# Signal.net
KiCad netlist of a schematic drawn in EAGLE
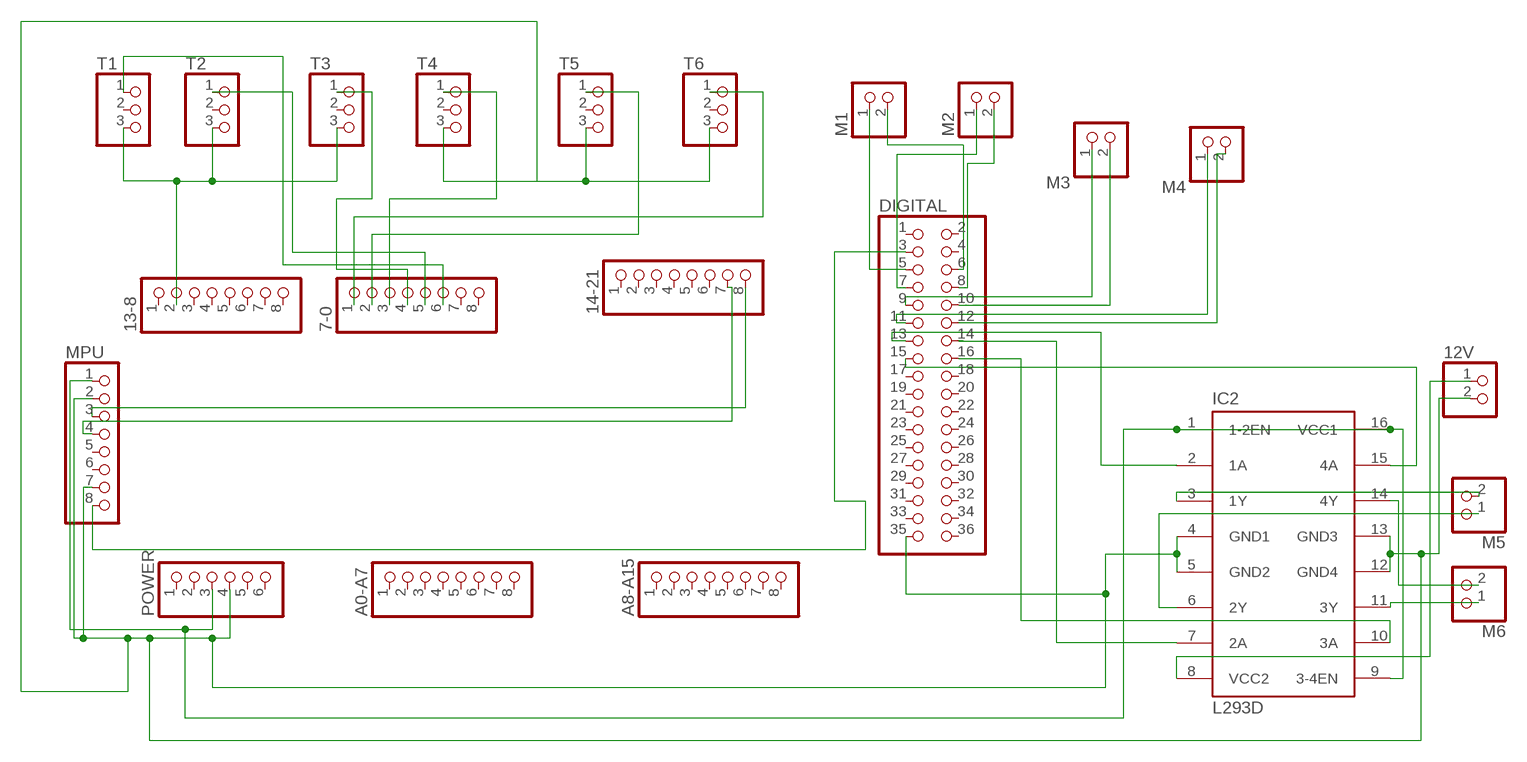
[diagram p0: schematic, sheet 1]

(export (version "E")
  (design (tool "Eeschema 10.0.6"))
  (components
    (comp (ref "7-0")
      (value "PINHD-1X8")
      (footprint "eagle-import:1X08")
      (libsource (lib "eagle-import") (part "PINHD-1X8"))
    )
    (comp (ref "12V")
      (value "PINHD-1X2")
      (footprint "eagle-import:1X02")
      (libsource (lib "eagle-import") (part "PINHD-1X2"))
    )
    (comp (ref "13-8")
      (value "PINHD-1X8")
      (footprint "eagle-import:1X08")
      (libsource (lib "eagle-import") (part "PINHD-1X8"))
    )
    (comp (ref "14-21")
      (value "PINHD-1X8")
      (footprint "eagle-import:1X08")
      (libsource (lib "eagle-import") (part "PINHD-1X8"))
    )
    (comp (ref "A0-A7")
      (value "PINHD-1X8")
      (footprint "eagle-import:1X08")
      (libsource (lib "eagle-import") (part "PINHD-1X8"))
    )
    (comp (ref "A8-A15")
      (value "PINHD-1X8")
      (footprint "eagle-import:1X08")
      (libsource (lib "eagle-import") (part "PINHD-1X8"))
    )
    (comp (ref "DIGITAL")
      (value "PINHD-2X18")
      (footprint "eagle-import:2X18")
      (libsource (lib "eagle-import") (part "PINHD-2X18"))
    )
    (comp (ref "IC2")
      (value "L293D")
      (footprint "eagle-import:DIL16")
      (libsource (lib "eagle-import") (part "L293D"))
    )
    (comp (ref "M1")
      (value "PINHD-1X2")
      (footprint "eagle-import:1X02")
      (libsource (lib "eagle-import") (part "PINHD-1X2"))
    )
    (comp (ref "M2")
      (value "PINHD-1X2")
      (footprint "eagle-import:1X02")
      (libsource (lib "eagle-import") (part "PINHD-1X2"))
    )
    (comp (ref "M3")
      (value "PINHD-1X2")
      (footprint "eagle-import:1X02")
      (libsource (lib "eagle-import") (part "PINHD-1X2"))
    )
    (comp (ref "M4")
      (value "PINHD-1X2")
      (footprint "eagle-import:1X02")
      (libsource (lib "eagle-import") (part "PINHD-1X2"))
    )
    (comp (ref "M5")
      (value "PINHD-1X2")
      (footprint "eagle-import:1X02")
      (libsource (lib "eagle-import") (part "PINHD-1X2"))
    )
    (comp (ref "M6")
      (value "PINHD-1X2")
      (footprint "eagle-import:1X02")
      (libsource (lib "eagle-import") (part "PINHD-1X2"))
    )
    (comp (ref "MPU")
      (value "PINHD-1X8")
      (footprint "eagle-import:1X08")
      (libsource (lib "eagle-import") (part "PINHD-1X8"))
    )
    (comp (ref "POWER")
      (value "PINHD-1X6")
      (footprint "eagle-import:1X06")
      (libsource (lib "eagle-import") (part "PINHD-1X6"))
    )
    (comp (ref "T1")
      (value "PINHD-1X3")
      (footprint "eagle-import:1X03")
      (libsource (lib "eagle-import") (part "PINHD-1X3"))
    )
    (comp (ref "T2")
      (value "PINHD-1X3")
      (footprint "eagle-import:1X03")
      (libsource (lib "eagle-import") (part "PINHD-1X3"))
    )
    (comp (ref "T3")
      (value "PINHD-1X3")
      (footprint "eagle-import:1X03")
      (libsource (lib "eagle-import") (part "PINHD-1X3"))
    )
    (comp (ref "T4")
      (value "PINHD-1X3")
      (footprint "eagle-import:1X03")
      (libsource (lib "eagle-import") (part "PINHD-1X3"))
    )
    (comp (ref "T5")
      (value "PINHD-1X3")
      (footprint "eagle-import:1X03")
      (libsource (lib "eagle-import") (part "PINHD-1X3"))
    )
    (comp (ref "T6")
      (value "PINHD-1X3")
      (footprint "eagle-import:1X03")
      (libsource (lib "eagle-import") (part "PINHD-1X3"))
    )
  )
  (nets
    (net (code "1") (name "Net-(7-0-Pad1)") (class "Default")
      (node (ref "7-0") (pin "1") (pinfunction "1_1") (pintype "passive"))
      (node (ref "T6") (pin "1") (pinfunction "1_1") (pintype "passive"))
    )
    (net (code "2") (name "Net-(7-0-Pad2)") (class "Default")
      (node (ref "7-0") (pin "2") (pinfunction "2_2") (pintype "passive"))
      (node (ref "T5") (pin "1") (pinfunction "1_1") (pintype "passive"))
    )
    (net (code "3") (name "Net-(7-0-Pad3)") (class "Default")
      (node (ref "7-0") (pin "3") (pinfunction "3_3") (pintype "passive"))
      (node (ref "T4") (pin "1") (pinfunction "1_1") (pintype "passive"))
    )
    (net (code "4") (name "Net-(7-0-Pad4)") (class "Default")
      (node (ref "7-0") (pin "4") (pinfunction "4_4") (pintype "passive"))
      (node (ref "T3") (pin "1") (pinfunction "1_1") (pintype "passive"))
    )
    (net (code "5") (name "Net-(7-0-Pad5)") (class "Default")
      (node (ref "7-0") (pin "5") (pinfunction "5_5") (pintype "passive"))
      (node (ref "T2") (pin "1") (pinfunction "1_1") (pintype "passive"))
    )
    (net (code "6") (name "Net-(7-0-Pad6)") (class "Default")
      (node (ref "7-0") (pin "6") (pinfunction "6_6") (pintype "passive"))
      (node (ref "T1") (pin "1") (pinfunction "1_1") (pintype "passive"))
    )
    (net (code "7") (name "Net-(13-8-Pad2)") (class "Default")
      (node (ref "13-8") (pin "2") (pinfunction "2_2") (pintype "passive"))
      (node (ref "T1") (pin "3") (pinfunction "3_3") (pintype "passive"))
      (node (ref "T2") (pin "3") (pinfunction "3_3") (pintype "passive"))
      (node (ref "T3") (pin "3") (pinfunction "3_3") (pintype "passive"))
    )
    (net (code "8") (name "Net-(14-21-Pad7)") (class "Default")
      (node (ref "14-21") (pin "7") (pinfunction "7_7") (pintype "passive"))
      (node (ref "MPU") (pin "4") (pinfunction "4_4") (pintype "passive"))
    )
    (net (code "9") (name "Net-(14-21-Pad8)") (class "Default")
      (node (ref "14-21") (pin "8") (pinfunction "8_8") (pintype "passive"))
      (node (ref "MPU") (pin "3") (pinfunction "3_3") (pintype "passive"))
    )
    (net (code "10") (name "Net-(DIGITAL-Pad3)") (class "Default")
      (node (ref "DIGITAL") (pin "3") (pinfunction "3_3") (pintype "passive"))
      (node (ref "MPU") (pin "8") (pinfunction "8_8") (pintype "passive"))
    )
    (net (code "11") (name "Net-(DIGITAL-Pad5)") (class "Default")
      (node (ref "DIGITAL") (pin "5") (pinfunction "5_5") (pintype "passive"))
      (node (ref "M1") (pin "1") (pinfunction "1_1") (pintype "passive"))
    )
    (net (code "12") (name "Net-(DIGITAL-Pad6)") (class "Default")
      (node (ref "DIGITAL") (pin "6") (pinfunction "6_6") (pintype "passive"))
      (node (ref "M1") (pin "2") (pinfunction "2_2") (pintype "passive"))
    )
    (net (code "13") (name "Net-(DIGITAL-Pad7)") (class "Default")
      (node (ref "DIGITAL") (pin "7") (pinfunction "7_7") (pintype "passive"))
      (node (ref "M2") (pin "1") (pinfunction "1_1") (pintype "passive"))
    )
    (net (code "14") (name "Net-(DIGITAL-Pad8)") (class "Default")
      (node (ref "DIGITAL") (pin "8") (pinfunction "8_8") (pintype "passive"))
      (node (ref "M2") (pin "2") (pinfunction "2_2") (pintype "passive"))
    )
    (net (code "15") (name "Net-(DIGITAL-Pad9)") (class "Default")
      (node (ref "DIGITAL") (pin "9") (pinfunction "9_9") (pintype "passive"))
      (node (ref "M3") (pin "1") (pinfunction "1_1") (pintype "passive"))
    )
    (net (code "16") (name "Net-(DIGITAL-Pad10)") (class "Default")
      (node (ref "DIGITAL") (pin "10") (pinfunction "10_10") (pintype "passive"))
      (node (ref "M3") (pin "2") (pinfunction "2_2") (pintype "passive"))
    )
    (net (code "17") (name "Net-(DIGITAL-Pad11)") (class "Default")
      (node (ref "DIGITAL") (pin "11") (pinfunction "11_11") (pintype "passive"))
      (node (ref "M4") (pin "1") (pinfunction "1_1") (pintype "passive"))
    )
    (net (code "18") (name "Net-(DIGITAL-Pad12)") (class "Default")
      (node (ref "DIGITAL") (pin "12") (pinfunction "12_12") (pintype "passive"))
      (node (ref "M4") (pin "2") (pinfunction "2_2") (pintype "passive"))
    )
    (net (code "19") (name "Net-(IC2-1-2EN)") (class "Default")
      (node (ref "IC2") (pin "1") (pinfunction "1-2EN_1") (pintype "input"))
      (node (ref "IC2") (pin "16") (pinfunction "VCC1_16") (pintype "power_in"))
      (node (ref "IC2") (pin "9") (pinfunction "3-4EN_9") (pintype "input"))
      (node (ref "MPU") (pin "1") (pinfunction "1_1") (pintype "passive"))
      (node (ref "POWER") (pin "3") (pinfunction "3_3") (pintype "passive"))
    )
    (net (code "20") (name "Net-(IC2-1A)") (class "Default")
      (node (ref "DIGITAL") (pin "13") (pinfunction "13_13") (pintype "passive"))
      (node (ref "IC2") (pin "2") (pinfunction "1A_2") (pintype "input"))
    )
    (net (code "21") (name "Net-(IC2-1Y)") (class "Default")
      (node (ref "IC2") (pin "3") (pinfunction "1Y_3") (pintype "output"))
      (node (ref "M5") (pin "2") (pinfunction "2_2") (pintype "passive"))
    )
    (net (code "22") (name "Net-(IC2-2A)") (class "Default")
      (node (ref "DIGITAL") (pin "14") (pinfunction "14_14") (pintype "passive"))
      (node (ref "IC2") (pin "7") (pinfunction "2A_7") (pintype "input"))
    )
    (net (code "23") (name "Net-(IC2-2Y)") (class "Default")
      (node (ref "IC2") (pin "6") (pinfunction "2Y_6") (pintype "output"))
      (node (ref "M5") (pin "1") (pinfunction "1_1") (pintype "passive"))
    )
    (net (code "24") (name "Net-(IC2-3A)") (class "Default")
      (node (ref "DIGITAL") (pin "16") (pinfunction "16_16") (pintype "passive"))
      (node (ref "IC2") (pin "10") (pinfunction "3A_10") (pintype "input"))
    )
    (net (code "25") (name "Net-(IC2-3Y)") (class "Default")
      (node (ref "IC2") (pin "11") (pinfunction "3Y_11") (pintype "output"))
      (node (ref "M6") (pin "1") (pinfunction "1_1") (pintype "passive"))
    )
    (net (code "26") (name "Net-(IC2-4A)") (class "Default")
      (node (ref "DIGITAL") (pin "15") (pinfunction "15_15") (pintype "passive"))
      (node (ref "IC2") (pin "15") (pinfunction "4A_15") (pintype "input"))
    )
    (net (code "27") (name "Net-(IC2-4Y)") (class "Default")
      (node (ref "IC2") (pin "14") (pinfunction "4Y_14") (pintype "output"))
      (node (ref "M6") (pin "2") (pinfunction "2_2") (pintype "passive"))
    )
    (net (code "28") (name "Net-(IC2-GND1)") (class "Default")
      (node (ref "12V") (pin "2") (pinfunction "2_2") (pintype "passive"))
      (node (ref "DIGITAL") (pin "35") (pinfunction "35_35") (pintype "passive"))
      (node (ref "IC2") (pin "12") (pinfunction "GND4_12") (pintype "power_in"))
      (node (ref "IC2") (pin "13") (pinfunction "GND3_13") (pintype "power_in"))
      (node (ref "IC2") (pin "4") (pinfunction "GND1_4") (pintype "power_in"))
      (node (ref "IC2") (pin "5") (pinfunction "GND2_5") (pintype "power_in"))
      (node (ref "MPU") (pin "2") (pinfunction "2_2") (pintype "passive"))
      (node (ref "MPU") (pin "7") (pinfunction "7_7") (pintype "passive"))
      (node (ref "POWER") (pin "4") (pinfunction "4_4") (pintype "passive"))
      (node (ref "T4") (pin "3") (pinfunction "3_3") (pintype "passive"))
      (node (ref "T5") (pin "3") (pinfunction "3_3") (pintype "passive"))
      (node (ref "T6") (pin "3") (pinfunction "3_3") (pintype "passive"))
    )
    (net (code "29") (name "Net-(IC2-VCC2)") (class "Default")
      (node (ref "12V") (pin "1") (pinfunction "1_1") (pintype "passive"))
      (node (ref "IC2") (pin "8") (pinfunction "VCC2_8") (pintype "power_in"))
    )
    (net (code "30") (name "unconnected-(7-0-Pad7)") (class "Default")
      (node (ref "7-0") (pin "7") (pinfunction "7_7") (pintype "passive"))
    )
    (net (code "31") (name "unconnected-(7-0-Pad8)") (class "Default")
      (node (ref "7-0") (pin "8") (pinfunction "8_8") (pintype "passive"))
    )
    (net (code "32") (name "unconnected-(13-8-Pad1)") (class "Default")
      (node (ref "13-8") (pin "1") (pinfunction "1_1") (pintype "passive"))
    )
    (net (code "33") (name "unconnected-(13-8-Pad3)") (class "Default")
      (node (ref "13-8") (pin "3") (pinfunction "3_3") (pintype "passive"))
    )
    (net (code "34") (name "unconnected-(13-8-Pad4)") (class "Default")
      (node (ref "13-8") (pin "4") (pinfunction "4_4") (pintype "passive"))
    )
    (net (code "35") (name "unconnected-(13-8-Pad5)") (class "Default")
      (node (ref "13-8") (pin "5") (pinfunction "5_5") (pintype "passive"))
    )
    (net (code "36") (name "unconnected-(13-8-Pad6)") (class "Default")
      (node (ref "13-8") (pin "6") (pinfunction "6_6") (pintype "passive"))
    )
    (net (code "37") (name "unconnected-(13-8-Pad7)") (class "Default")
      (node (ref "13-8") (pin "7") (pinfunction "7_7") (pintype "passive"))
    )
    (net (code "38") (name "unconnected-(13-8-Pad8)") (class "Default")
      (node (ref "13-8") (pin "8") (pinfunction "8_8") (pintype "passive"))
    )
    (net (code "39") (name "unconnected-(14-21-Pad1)") (class "Default")
      (node (ref "14-21") (pin "1") (pinfunction "1_1") (pintype "passive"))
    )
    (net (code "40") (name "unconnected-(14-21-Pad2)") (class "Default")
      (node (ref "14-21") (pin "2") (pinfunction "2_2") (pintype "passive"))
    )
    (net (code "41") (name "unconnected-(14-21-Pad3)") (class "Default")
      (node (ref "14-21") (pin "3") (pinfunction "3_3") (pintype "passive"))
    )
    (net (code "42") (name "unconnected-(14-21-Pad4)") (class "Default")
      (node (ref "14-21") (pin "4") (pinfunction "4_4") (pintype "passive"))
    )
    (net (code "43") (name "unconnected-(14-21-Pad5)") (class "Default")
      (node (ref "14-21") (pin "5") (pinfunction "5_5") (pintype "passive"))
    )
    (net (code "44") (name "unconnected-(14-21-Pad6)") (class "Default")
      (node (ref "14-21") (pin "6") (pinfunction "6_6") (pintype "passive"))
    )
    (net (code "45") (name "unconnected-(A0-A7-Pad1)") (class "Default")
      (node (ref "A0-A7") (pin "1") (pinfunction "1_1") (pintype "passive"))
    )
    (net (code "46") (name "unconnected-(A0-A7-Pad2)") (class "Default")
      (node (ref "A0-A7") (pin "2") (pinfunction "2_2") (pintype "passive"))
    )
    (net (code "47") (name "unconnected-(A0-A7-Pad3)") (class "Default")
      (node (ref "A0-A7") (pin "3") (pinfunction "3_3") (pintype "passive"))
    )
    (net (code "48") (name "unconnected-(A0-A7-Pad4)") (class "Default")
      (node (ref "A0-A7") (pin "4") (pinfunction "4_4") (pintype "passive"))
    )
    (net (code "49") (name "unconnected-(A0-A7-Pad5)") (class "Default")
      (node (ref "A0-A7") (pin "5") (pinfunction "5_5") (pintype "passive"))
    )
    (net (code "50") (name "unconnected-(A0-A7-Pad6)") (class "Default")
      (node (ref "A0-A7") (pin "6") (pinfunction "6_6") (pintype "passive"))
    )
    (net (code "51") (name "unconnected-(A0-A7-Pad7)") (class "Default")
      (node (ref "A0-A7") (pin "7") (pinfunction "7_7") (pintype "passive"))
    )
    (net (code "52") (name "unconnected-(A0-A7-Pad8)") (class "Default")
      (node (ref "A0-A7") (pin "8") (pinfunction "8_8") (pintype "passive"))
    )
    (net (code "53") (name "unconnected-(A8-A15-Pad1)") (class "Default")
      (node (ref "A8-A15") (pin "1") (pinfunction "1_1") (pintype "passive"))
    )
    (net (code "54") (name "unconnected-(A8-A15-Pad2)") (class "Default")
      (node (ref "A8-A15") (pin "2") (pinfunction "2_2") (pintype "passive"))
    )
    (net (code "55") (name "unconnected-(A8-A15-Pad3)") (class "Default")
      (node (ref "A8-A15") (pin "3") (pinfunction "3_3") (pintype "passive"))
    )
    (net (code "56") (name "unconnected-(A8-A15-Pad4)") (class "Default")
      (node (ref "A8-A15") (pin "4") (pinfunction "4_4") (pintype "passive"))
    )
    (net (code "57") (name "unconnected-(A8-A15-Pad5)") (class "Default")
      (node (ref "A8-A15") (pin "5") (pinfunction "5_5") (pintype "passive"))
    )
    (net (code "58") (name "unconnected-(A8-A15-Pad6)") (class "Default")
      (node (ref "A8-A15") (pin "6") (pinfunction "6_6") (pintype "passive"))
    )
    (net (code "59") (name "unconnected-(A8-A15-Pad7)") (class "Default")
      (node (ref "A8-A15") (pin "7") (pinfunction "7_7") (pintype "passive"))
    )
    (net (code "60") (name "unconnected-(A8-A15-Pad8)") (class "Default")
      (node (ref "A8-A15") (pin "8") (pinfunction "8_8") (pintype "passive"))
    )
    (net (code "61") (name "unconnected-(DIGITAL-Pad1)") (class "Default")
      (node (ref "DIGITAL") (pin "1") (pinfunction "1_1") (pintype "passive"))
    )
    (net (code "62") (name "unconnected-(DIGITAL-Pad2)") (class "Default")
      (node (ref "DIGITAL") (pin "2") (pinfunction "2_2") (pintype "passive"))
    )
    (net (code "63") (name "unconnected-(DIGITAL-Pad4)") (class "Default")
      (node (ref "DIGITAL") (pin "4") (pinfunction "4_4") (pintype "passive"))
    )
    (net (code "64") (name "unconnected-(DIGITAL-Pad17)") (class "Default")
      (node (ref "DIGITAL") (pin "17") (pinfunction "17_17") (pintype "passive"))
    )
    (net (code "65") (name "unconnected-(DIGITAL-Pad18)") (class "Default")
      (node (ref "DIGITAL") (pin "18") (pinfunction "18_18") (pintype "passive"))
    )
    (net (code "66") (name "unconnected-(DIGITAL-Pad19)") (class "Default")
      (node (ref "DIGITAL") (pin "19") (pinfunction "19_19") (pintype "passive"))
    )
    (net (code "67") (name "unconnected-(DIGITAL-Pad20)") (class "Default")
      (node (ref "DIGITAL") (pin "20") (pinfunction "20_20") (pintype "passive"))
    )
    (net (code "68") (name "unconnected-(DIGITAL-Pad21)") (class "Default")
      (node (ref "DIGITAL") (pin "21") (pinfunction "21_21") (pintype "passive"))
    )
    (net (code "69") (name "unconnected-(DIGITAL-Pad22)") (class "Default")
      (node (ref "DIGITAL") (pin "22") (pinfunction "22_22") (pintype "passive"))
    )
    (net (code "70") (name "unconnected-(DIGITAL-Pad23)") (class "Default")
      (node (ref "DIGITAL") (pin "23") (pinfunction "23_23") (pintype "passive"))
    )
    (net (code "71") (name "unconnected-(DIGITAL-Pad24)") (class "Default")
      (node (ref "DIGITAL") (pin "24") (pinfunction "24_24") (pintype "passive"))
    )
    (net (code "72") (name "unconnected-(DIGITAL-Pad25)") (class "Default")
      (node (ref "DIGITAL") (pin "25") (pinfunction "25_25") (pintype "passive"))
    )
    (net (code "73") (name "unconnected-(DIGITAL-Pad26)") (class "Default")
      (node (ref "DIGITAL") (pin "26") (pinfunction "26_26") (pintype "passive"))
    )
    (net (code "74") (name "unconnected-(DIGITAL-Pad27)") (class "Default")
      (node (ref "DIGITAL") (pin "27") (pinfunction "27_27") (pintype "passive"))
    )
    (net (code "75") (name "unconnected-(DIGITAL-Pad28)") (class "Default")
      (node (ref "DIGITAL") (pin "28") (pinfunction "28_28") (pintype "passive"))
    )
    (net (code "76") (name "unconnected-(DIGITAL-Pad29)") (class "Default")
      (node (ref "DIGITAL") (pin "29") (pinfunction "29_29") (pintype "passive"))
    )
    (net (code "77") (name "unconnected-(DIGITAL-Pad30)") (class "Default")
      (node (ref "DIGITAL") (pin "30") (pinfunction "30_30") (pintype "passive"))
    )
    (net (code "78") (name "unconnected-(DIGITAL-Pad31)") (class "Default")
      (node (ref "DIGITAL") (pin "31") (pinfunction "31_31") (pintype "passive"))
    )
    (net (code "79") (name "unconnected-(DIGITAL-Pad32)") (class "Default")
      (node (ref "DIGITAL") (pin "32") (pinfunction "32_32") (pintype "passive"))
    )
    (net (code "80") (name "unconnected-(DIGITAL-Pad33)") (class "Default")
      (node (ref "DIGITAL") (pin "33") (pinfunction "33_33") (pintype "passive"))
    )
    (net (code "81") (name "unconnected-(DIGITAL-Pad34)") (class "Default")
      (node (ref "DIGITAL") (pin "34") (pinfunction "34_34") (pintype "passive"))
    )
    (net (code "82") (name "unconnected-(DIGITAL-Pad36)") (class "Default")
      (node (ref "DIGITAL") (pin "36") (pinfunction "36_36") (pintype "passive"))
    )
    (net (code "83") (name "unconnected-(MPU-Pad5)") (class "Default")
      (node (ref "MPU") (pin "5") (pinfunction "5_5") (pintype "passive"))
    )
    (net (code "84") (name "unconnected-(MPU-Pad6)") (class "Default")
      (node (ref "MPU") (pin "6") (pinfunction "6_6") (pintype "passive"))
    )
    (net (code "85") (name "unconnected-(POWER-Pad1)") (class "Default")
      (node (ref "POWER") (pin "1") (pinfunction "1_1") (pintype "passive"))
    )
    (net (code "86") (name "unconnected-(POWER-Pad2)") (class "Default")
      (node (ref "POWER") (pin "2") (pinfunction "2_2") (pintype "passive"))
    )
    (net (code "87") (name "unconnected-(POWER-Pad5)") (class "Default")
      (node (ref "POWER") (pin "5") (pinfunction "5_5") (pintype "passive"))
    )
    (net (code "88") (name "unconnected-(POWER-Pad6)") (class "Default")
      (node (ref "POWER") (pin "6") (pinfunction "6_6") (pintype "passive"))
    )
    (net (code "89") (name "unconnected-(T1-Pad2)") (class "Default")
      (node (ref "T1") (pin "2") (pinfunction "2_2") (pintype "passive"))
    )
    (net (code "90") (name "unconnected-(T2-Pad2)") (class "Default")
      (node (ref "T2") (pin "2") (pinfunction "2_2") (pintype "passive"))
    )
    (net (code "91") (name "unconnected-(T3-Pad2)") (class "Default")
      (node (ref "T3") (pin "2") (pinfunction "2_2") (pintype "passive"))
    )
    (net (code "92") (name "unconnected-(T4-Pad2)") (class "Default")
      (node (ref "T4") (pin "2") (pinfunction "2_2") (pintype "passive"))
    )
    (net (code "93") (name "unconnected-(T5-Pad2)") (class "Default")
      (node (ref "T5") (pin "2") (pinfunction "2_2") (pintype "passive"))
    )
    (net (code "94") (name "unconnected-(T6-Pad2)") (class "Default")
      (node (ref "T6") (pin "2") (pinfunction "2_2") (pintype "passive"))
    )
  )
)
